# Cursor-EC60.net
KiCad netlist of a schematic drawn in EAGLE
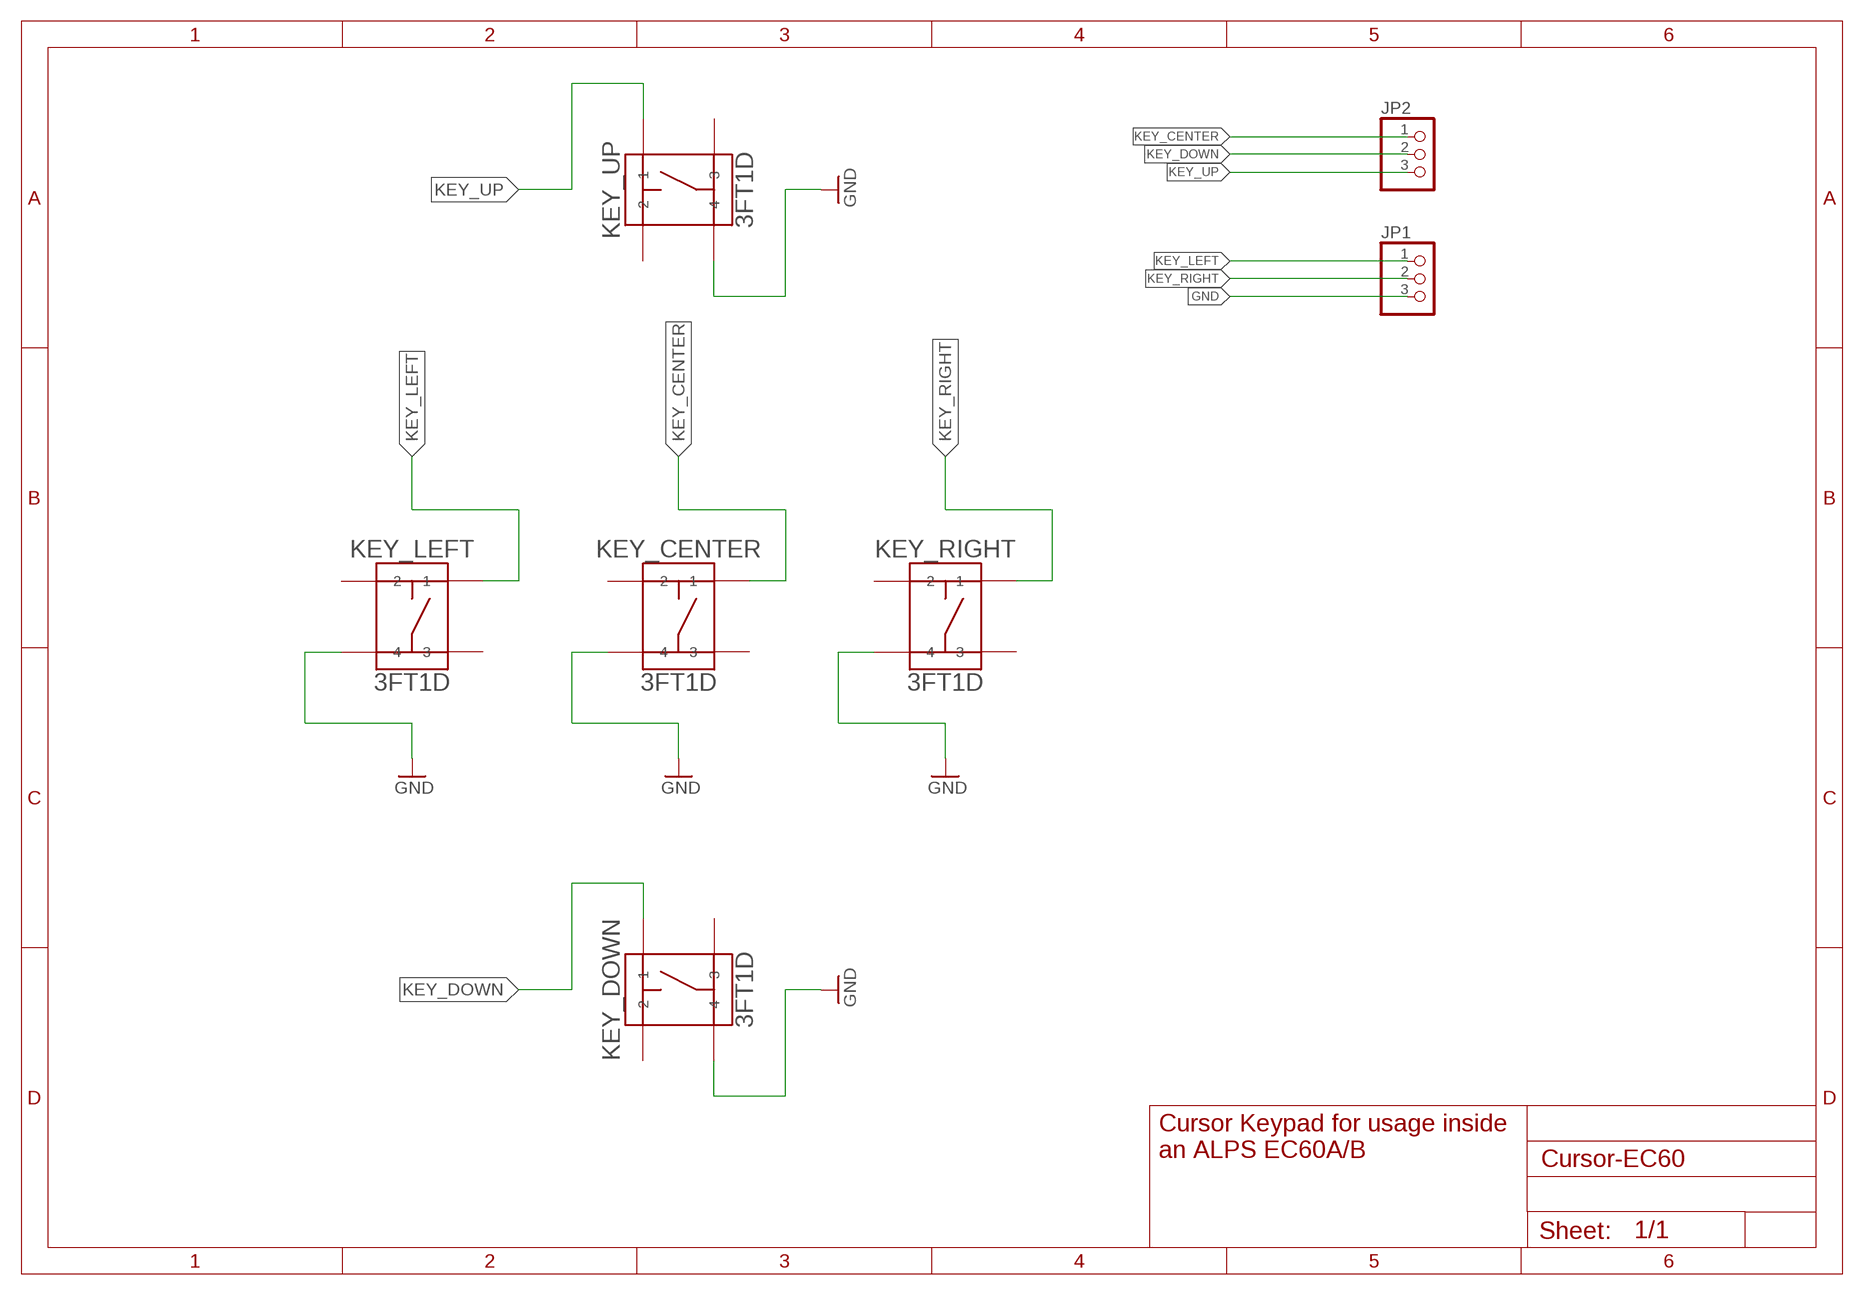
[diagram p0: schematic, sheet 1]

(export (version "E")
  (design (tool "Eeschema 10.0.6"))
  (components
    (comp (ref "JP1")
      (value "PINHD-1X3")
      (footprint "eagle-import:1X03")
      (libsource (lib "eagle-import") (part "PINHD-1X3"))
    )
    (comp (ref "JP2")
      (value "PINHD-1X3")
      (footprint "eagle-import:1X03")
      (libsource (lib "eagle-import") (part "PINHD-1X3"))
    )
    (comp (ref "KEY_CENTER")
      (value "3FT1D")
      (footprint "eagle-import:3FT")
      (libsource (lib "eagle-import") (part "3FT1D"))
    )
    (comp (ref "KEY_DOWN")
      (value "3FT1D")
      (footprint "eagle-import:3FT")
      (libsource (lib "eagle-import") (part "3FT1D"))
    )
    (comp (ref "KEY_LEFT")
      (value "3FT1D")
      (footprint "eagle-import:3FT")
      (libsource (lib "eagle-import") (part "3FT1D"))
    )
    (comp (ref "KEY_RIGHT")
      (value "3FT1D")
      (footprint "eagle-import:3FT")
      (libsource (lib "eagle-import") (part "3FT1D"))
    )
    (comp (ref "KEY_UP")
      (value "3FT1D")
      (footprint "eagle-import:3FT")
      (libsource (lib "eagle-import") (part "3FT1D"))
    )
  )
  (nets
    (net (code "1") (name "GND") (class "Default")
      (node (ref "JP1") (pin "3") (pinfunction "3_3") (pintype "passive"))
      (node (ref "KEY_CENTER") (pin "P$4") (pinfunction "4_P$4") (pintype "bidirectional"))
      (node (ref "KEY_DOWN") (pin "P$4") (pinfunction "4_P$4") (pintype "bidirectional"))
      (node (ref "KEY_LEFT") (pin "P$4") (pinfunction "4_P$4") (pintype "bidirectional"))
      (node (ref "KEY_RIGHT") (pin "P$4") (pinfunction "4_P$4") (pintype "bidirectional"))
      (node (ref "KEY_UP") (pin "P$4") (pinfunction "4_P$4") (pintype "bidirectional"))
    )
    (net (code "2") (name "KEY_CENTER") (class "Default")
      (node (ref "JP2") (pin "1") (pinfunction "1_1") (pintype "passive"))
      (node (ref "KEY_CENTER") (pin "P$1") (pinfunction "1_P$1") (pintype "bidirectional"))
    )
    (net (code "3") (name "KEY_DOWN") (class "Default")
      (node (ref "JP2") (pin "2") (pinfunction "2_2") (pintype "passive"))
      (node (ref "KEY_DOWN") (pin "P$1") (pinfunction "1_P$1") (pintype "bidirectional"))
    )
    (net (code "4") (name "KEY_LEFT") (class "Default")
      (node (ref "JP1") (pin "1") (pinfunction "1_1") (pintype "passive"))
      (node (ref "KEY_LEFT") (pin "P$1") (pinfunction "1_P$1") (pintype "bidirectional"))
    )
    (net (code "5") (name "KEY_RIGHT") (class "Default")
      (node (ref "JP1") (pin "2") (pinfunction "2_2") (pintype "passive"))
      (node (ref "KEY_RIGHT") (pin "P$1") (pinfunction "1_P$1") (pintype "bidirectional"))
    )
    (net (code "6") (name "KEY_UP") (class "Default")
      (node (ref "JP2") (pin "3") (pinfunction "3_3") (pintype "passive"))
      (node (ref "KEY_UP") (pin "P$1") (pinfunction "1_P$1") (pintype "bidirectional"))
    )
    (net (code "7") (name "unconnected-(KEY_CENTER-2-PadP$2)") (class "Default")
      (node (ref "KEY_CENTER") (pin "P$2") (pinfunction "2_P$2") (pintype "bidirectional"))
    )
    (net (code "8") (name "unconnected-(KEY_CENTER-3-PadP$3)") (class "Default")
      (node (ref "KEY_CENTER") (pin "P$3") (pinfunction "3_P$3") (pintype "bidirectional"))
    )
    (net (code "9") (name "unconnected-(KEY_DOWN-2-PadP$2)") (class "Default")
      (node (ref "KEY_DOWN") (pin "P$2") (pinfunction "2_P$2") (pintype "bidirectional"))
    )
    (net (code "10") (name "unconnected-(KEY_DOWN-3-PadP$3)") (class "Default")
      (node (ref "KEY_DOWN") (pin "P$3") (pinfunction "3_P$3") (pintype "bidirectional"))
    )
    (net (code "11") (name "unconnected-(KEY_LEFT-2-PadP$2)") (class "Default")
      (node (ref "KEY_LEFT") (pin "P$2") (pinfunction "2_P$2") (pintype "bidirectional"))
    )
    (net (code "12") (name "unconnected-(KEY_LEFT-3-PadP$3)") (class "Default")
      (node (ref "KEY_LEFT") (pin "P$3") (pinfunction "3_P$3") (pintype "bidirectional"))
    )
    (net (code "13") (name "unconnected-(KEY_RIGHT-2-PadP$2)") (class "Default")
      (node (ref "KEY_RIGHT") (pin "P$2") (pinfunction "2_P$2") (pintype "bidirectional"))
    )
    (net (code "14") (name "unconnected-(KEY_RIGHT-3-PadP$3)") (class "Default")
      (node (ref "KEY_RIGHT") (pin "P$3") (pinfunction "3_P$3") (pintype "bidirectional"))
    )
    (net (code "15") (name "unconnected-(KEY_UP-2-PadP$2)") (class "Default")
      (node (ref "KEY_UP") (pin "P$2") (pinfunction "2_P$2") (pintype "bidirectional"))
    )
    (net (code "16") (name "unconnected-(KEY_UP-3-PadP$3)") (class "Default")
      (node (ref "KEY_UP") (pin "P$3") (pinfunction "3_P$3") (pintype "bidirectional"))
    )
  )
)
